# B3PIC_picfinalcurrentreading.net
KiCad netlist of a schematic drawn in EAGLE
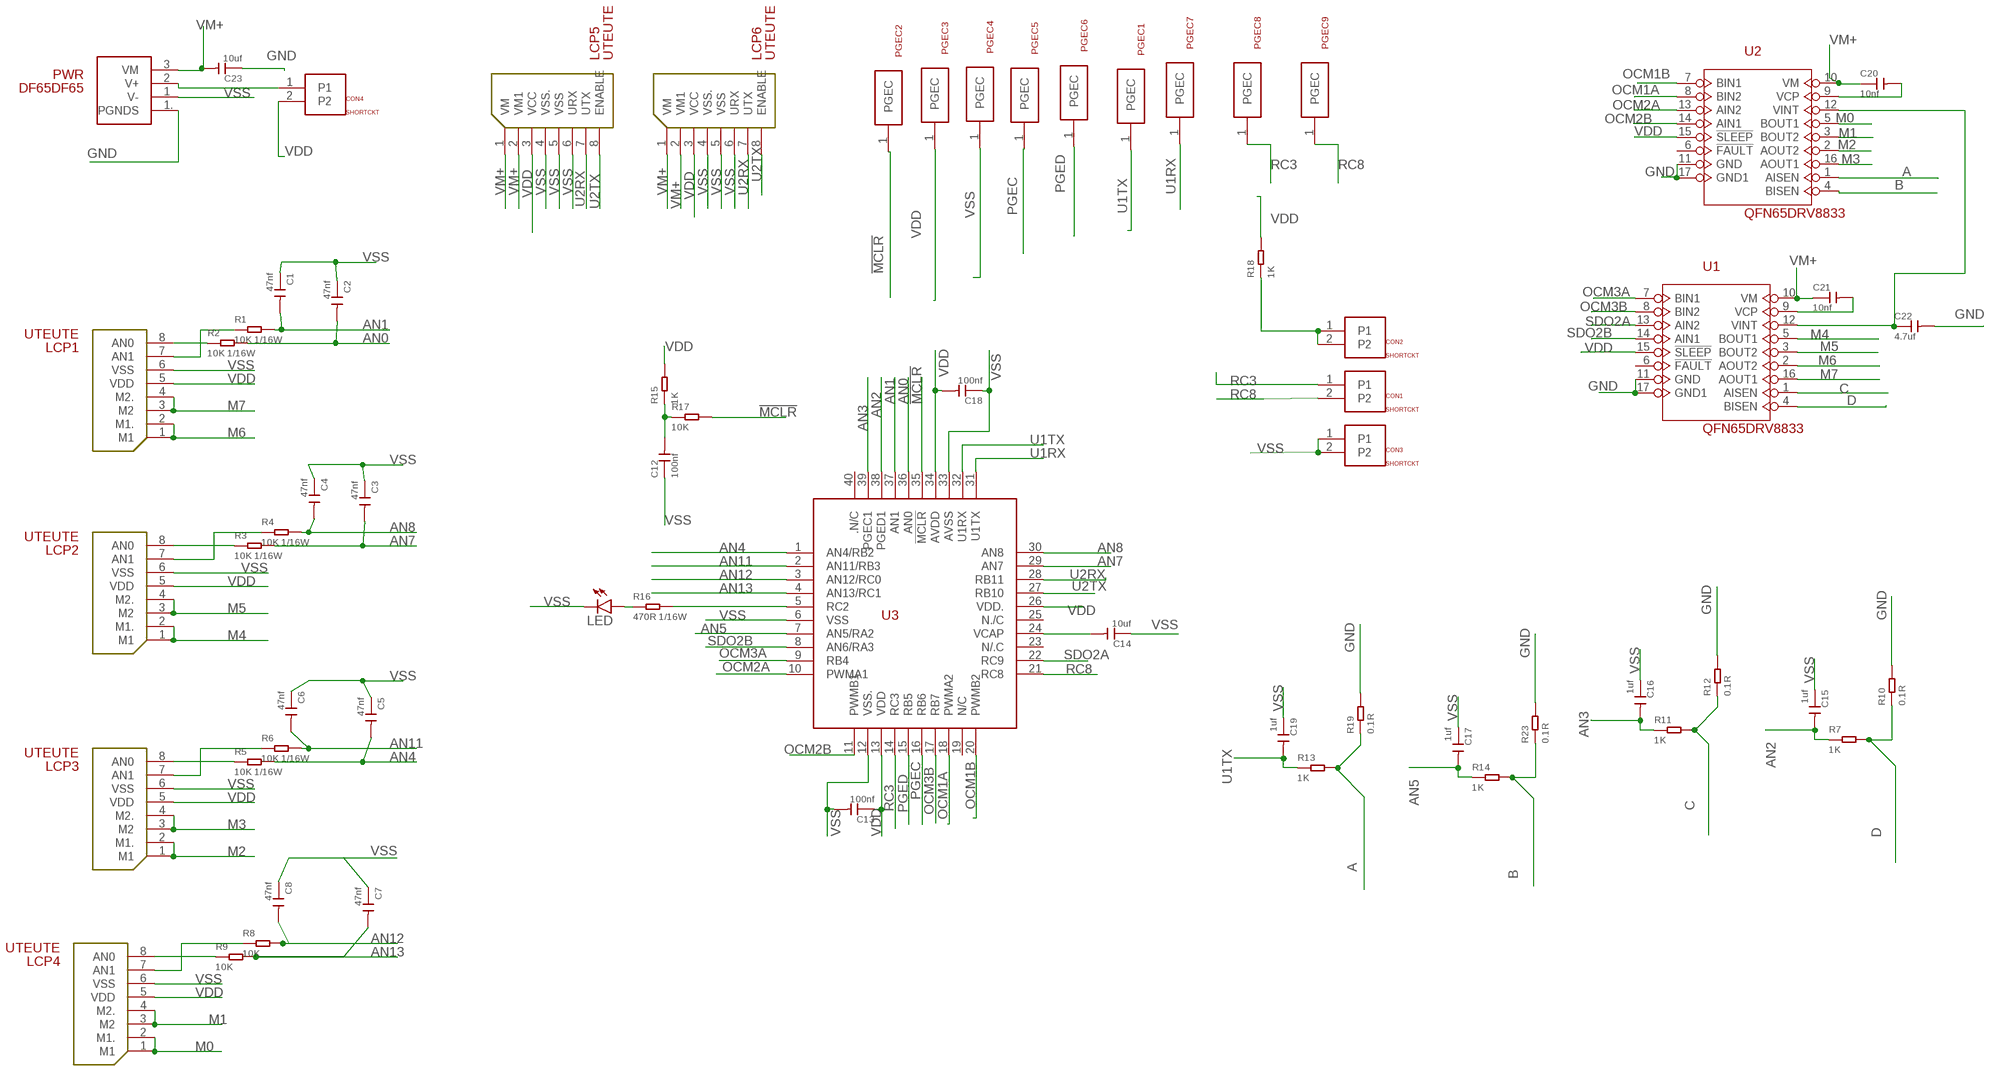
[diagram p0: schematic, sheet 1]

(export (version "E")
  (design (tool "Eeschema 10.0.6"))
  (components
    (comp (ref "C1")
      (value "47nf")
      (footprint "eagle-import:C0402")
      (fields (field (name "MPN") "CC0402KRX7R8BB473"))
      (libsource (lib "eagle-import") (part "CERAMIC-47NF-25V-10%-X7R(0402)"))
    )
    (comp (ref "C2")
      (value "47nf")
      (footprint "eagle-import:C0402")
      (fields (field (name "MPN") "CC0402KRX7R8BB473"))
      (libsource (lib "eagle-import") (part "CERAMIC-47NF-25V-10%-X7R(0402)"))
    )
    (comp (ref "C3")
      (value "47nf")
      (footprint "eagle-import:C0402")
      (fields (field (name "MPN") "CC0402KRX7R8BB473"))
      (libsource (lib "eagle-import") (part "CERAMIC-47NF-25V-10%-X7R(0402)"))
    )
    (comp (ref "C4")
      (value "47nf")
      (footprint "eagle-import:C0402")
      (fields (field (name "MPN") "CC0402KRX7R8BB473"))
      (libsource (lib "eagle-import") (part "CERAMIC-47NF-25V-10%-X7R(0402)"))
    )
    (comp (ref "C5")
      (value "47nf")
      (footprint "eagle-import:C0402")
      (fields (field (name "MPN") "CC0402KRX7R8BB473"))
      (libsource (lib "eagle-import") (part "CERAMIC-47NF-25V-10%-X7R(0402)"))
    )
    (comp (ref "C6")
      (value "47nf")
      (footprint "eagle-import:C0402")
      (fields (field (name "MPN") "CC0402KRX7R8BB473"))
      (libsource (lib "eagle-import") (part "CERAMIC-47NF-25V-10%-X7R(0402)"))
    )
    (comp (ref "C7")
      (value "47nf")
      (footprint "eagle-import:C0402")
      (fields (field (name "MPN") "CC0402KRX7R8BB473"))
      (libsource (lib "eagle-import") (part "CERAMIC-47NF-25V-10%-X7R(0402)"))
    )
    (comp (ref "C8")
      (value "47nf")
      (footprint "eagle-import:C0402")
      (fields (field (name "MPN") "CC0402KRX7R8BB473"))
      (libsource (lib "eagle-import") (part "CERAMIC-47NF-25V-10%-X7R(0402)"))
    )
    (comp (ref "C12")
      (value "100nf")
      (footprint "eagle-import:C0402")
      (fields (field (name "MPN") "CC0402KRX7R8BB104"))
      (libsource (lib "eagle-import") (part "CERAMIC-100NF-25V-10%-X7R(0402)"))
    )
    (comp (ref "C13")
      (value "100nf")
      (footprint "eagle-import:C0402")
      (fields (field (name "MPN") "CC0402KRX7R8BB104"))
      (libsource (lib "eagle-import") (part "CERAMIC-100NF-25V-10%-X7R(0402)"))
    )
    (comp (ref "C14")
      (value "10uf")
      (footprint "eagle-import:C0402")
      (fields (field (name "MPN") "CC0402MRX5R5BB106"))
      (libsource (lib "eagle-import") (part "CERAMIC-10UF-6.3V-20%-X5R(0402)"))
    )
    (comp (ref "C15")
      (value "1uf")
      (footprint "eagle-import:C0402")
      (fields (field (name "MPN") "CC0402KRX5R6BB105"))
      (libsource (lib "eagle-import") (part "CERAMIC-1UF-10V-10%-X5R(0402)"))
    )
    (comp (ref "C16")
      (value "1uf")
      (footprint "eagle-import:C0402")
      (fields (field (name "MPN") "CC0402KRX5R6BB105"))
      (libsource (lib "eagle-import") (part "CERAMIC-1UF-10V-10%-X5R(0402)"))
    )
    (comp (ref "C17")
      (value "1uf")
      (footprint "eagle-import:C0402")
      (fields (field (name "MPN") "CC0402KRX5R6BB105"))
      (libsource (lib "eagle-import") (part "CERAMIC-1UF-10V-10%-X5R(0402)"))
    )
    (comp (ref "C18")
      (value "100nf")
      (footprint "eagle-import:C0402")
      (fields (field (name "MPN") "CC0402KRX7R8BB104"))
      (libsource (lib "eagle-import") (part "CERAMIC-100NF-25V-10%-X7R(0402)"))
    )
    (comp (ref "C19")
      (value "1uf")
      (footprint "eagle-import:C0402")
      (fields (field (name "MPN") "CC0402KRX5R6BB105"))
      (libsource (lib "eagle-import") (part "CERAMIC-1UF-10V-10%-X5R(0402)"))
    )
    (comp (ref "C20")
      (value "10nf")
      (footprint "eagle-import:C0402")
      (fields (field (name "MPN") "CC0402KRX7R9BB103"))
      (libsource (lib "eagle-import") (part "CERAMIC-10NF-50V-10%-X7R(0402)"))
    )
    (comp (ref "C21")
      (value "10nf")
      (footprint "eagle-import:C0402")
      (fields (field (name "MPN") "CC0402KRX7R9BB103"))
      (libsource (lib "eagle-import") (part "CERAMIC-10NF-50V-10%-X7R(0402)"))
    )
    (comp (ref "C22")
      (value "4.7uf")
      (footprint "eagle-import:C0402")
      (fields (field (name "MPN") "CC0402MRX5R5BB475"))
      (libsource (lib "eagle-import") (part "CERAMIC-4.7UF-6.3V-20%-X5R(0402)"))
    )
    (comp (ref "C23")
      (value "10uf")
      (footprint "eagle-import:C0402")
      (fields (field (name "MPN") "CC0402MRX5R5BB106"))
      (libsource (lib "eagle-import") (part "CERAMIC-10UF-6.3V-20%-X5R(0402)"))
    )
    (comp (ref "CON1")
      (value "SHORTCKT")
      (footprint "eagle-import:SHORT")
      (libsource (lib "eagle-import") (part "SHORTCKT"))
    )
    (comp (ref "CON2")
      (value "SHORTCKT")
      (footprint "eagle-import:SHORT")
      (libsource (lib "eagle-import") (part "SHORTCKT"))
    )
    (comp (ref "CON3")
      (value "SHORTCKT")
      (footprint "eagle-import:SHORT")
      (libsource (lib "eagle-import") (part "SHORTCKT"))
    )
    (comp (ref "CON4")
      (value "SHORTCKT")
      (footprint "eagle-import:SHORT")
      (libsource (lib "eagle-import") (part "SHORTCKT"))
    )
    (comp (ref "LCP1")
      (value "UTEUTE")
      (footprint "eagle-import:UTE")
      (libsource (lib "eagle-import") (part "UTEUTE"))
    )
    (comp (ref "LCP2")
      (value "UTEUTE")
      (footprint "eagle-import:UTE")
      (libsource (lib "eagle-import") (part "UTEUTE"))
    )
    (comp (ref "LCP3")
      (value "UTEUTE")
      (footprint "eagle-import:UTE")
      (libsource (lib "eagle-import") (part "UTEUTE"))
    )
    (comp (ref "LCP4")
      (value "UTEUTE")
      (footprint "eagle-import:UTE")
      (libsource (lib "eagle-import") (part "UTEUTE"))
    )
    (comp (ref "LCP5")
      (value "UTEUTE")
      (footprint "eagle-import:UTE")
      (libsource (lib "eagle-import") (part "ute5526(uart)_UTEUTE"))
    )
    (comp (ref "LCP6")
      (value "UTEUTE")
      (footprint "eagle-import:UTE")
      (libsource (lib "eagle-import") (part "ute5526(uart)_UTEUTE"))
    )
    (comp (ref "LED")
      (value "LEDCHIP-LED0603")
      (footprint "eagle-import:CHIP-LED0603")
      (libsource (lib "eagle-import") (part "LEDCHIP-LED0603"))
    )
    (comp (ref "PGEC1")
      (value "PGECPGEC")
      (footprint "eagle-import:PGEC")
      (libsource (lib "eagle-import") (part "PGECPGEC"))
    )
    (comp (ref "PGEC2")
      (value "PGECPGEC")
      (footprint "eagle-import:PGEC")
      (libsource (lib "eagle-import") (part "PGECPGEC"))
    )
    (comp (ref "PGEC3")
      (value "PGECPGEC")
      (footprint "eagle-import:PGEC")
      (libsource (lib "eagle-import") (part "PGECPGEC"))
    )
    (comp (ref "PGEC4")
      (value "PGECPGEC")
      (footprint "eagle-import:PGEC")
      (libsource (lib "eagle-import") (part "PGECPGEC"))
    )
    (comp (ref "PGEC5")
      (value "PGECPGEC")
      (footprint "eagle-import:PGEC")
      (libsource (lib "eagle-import") (part "PGECPGEC"))
    )
    (comp (ref "PGEC6")
      (value "PGECPGEC")
      (footprint "eagle-import:PGEC")
      (libsource (lib "eagle-import") (part "PGECPGEC"))
    )
    (comp (ref "PGEC7")
      (value "PGECPGEC")
      (footprint "eagle-import:PGEC")
      (libsource (lib "eagle-import") (part "PGECPGEC"))
    )
    (comp (ref "PGEC8")
      (value "PGECPGEC")
      (footprint "eagle-import:PGEC")
      (libsource (lib "eagle-import") (part "PGECPGEC"))
    )
    (comp (ref "PGEC9")
      (value "PGECPGEC")
      (footprint "eagle-import:PGEC")
      (libsource (lib "eagle-import") (part "PGECPGEC"))
    )
    (comp (ref "PWR")
      (value "DF65DF65")
      (footprint "eagle-import:DF65")
      (libsource (lib "eagle-import") (part "DF65DF65"))
    )
    (comp (ref "R1")
      (value "10K 1/16W")
      (footprint "eagle-import:R0402")
      (fields (field (name "MPN") "RC0402FR-0710KL"))
      (libsource (lib "eagle-import") (part "SMD-RES-10K-1%-1/16W(0402)"))
    )
    (comp (ref "R2")
      (value "10K 1/16W")
      (footprint "eagle-import:R0402")
      (fields (field (name "MPN") "RC0402FR-0710KL"))
      (libsource (lib "eagle-import") (part "SMD-RES-10K-1%-1/16W(0402)"))
    )
    (comp (ref "R3")
      (value "10K 1/16W")
      (footprint "eagle-import:R0402")
      (fields (field (name "MPN") "RC0402FR-0710KL"))
      (libsource (lib "eagle-import") (part "SMD-RES-10K-1%-1/16W(0402)"))
    )
    (comp (ref "R4")
      (value "10K 1/16W")
      (footprint "eagle-import:R0402")
      (fields (field (name "MPN") "RC0402FR-0710KL"))
      (libsource (lib "eagle-import") (part "SMD-RES-10K-1%-1/16W(0402)"))
    )
    (comp (ref "R5")
      (value "10K 1/16W")
      (footprint "eagle-import:R0402")
      (fields (field (name "MPN") "RC0402FR-0710KL"))
      (libsource (lib "eagle-import") (part "SMD-RES-10K-1%-1/16W(0402)"))
    )
    (comp (ref "R6")
      (value "10K 1/16W")
      (footprint "eagle-import:R0402")
      (fields (field (name "MPN") "RC0402FR-0710KL"))
      (libsource (lib "eagle-import") (part "SMD-RES-10K-1%-1/16W(0402)"))
    )
    (comp (ref "R7")
      (value "1K")
      (footprint "eagle-import:R0402")
      (fields (field (name "MPN") "RC0402JR-071KL"))
      (libsource (lib "eagle-import") (part "SMD-RES-1K-5%-1/16W(0402)"))
    )
    (comp (ref "R8")
      (value "10K")
      (footprint "eagle-import:R0402")
      (fields (field (name "MPN") "RC0402JR-0710KL"))
      (libsource (lib "eagle-import") (part "SMD-RES-10K-5%-1/(0402)"))
    )
    (comp (ref "R9")
      (value "10K")
      (footprint "eagle-import:R0402")
      (fields (field (name "MPN") "RC0402JR-0710KL"))
      (libsource (lib "eagle-import") (part "SMD-RES-10K-5%-1/(0402)"))
    )
    (comp (ref "R10")
      (value "0.1R")
      (footprint "eagle-import:R0805")
      (fields (field (name "MPN") "RL0805JR-070R1L"))
      (libsource (lib "eagle-import") (part "SMD-RES-0.1R-5%-1/8W(0805)"))
    )
    (comp (ref "R11")
      (value "1K")
      (footprint "eagle-import:R0402")
      (fields (field (name "MPN") "RC0402JR-071KL"))
      (libsource (lib "eagle-import") (part "SMD-RES-1K-5%-1/16W(0402)"))
    )
    (comp (ref "R12")
      (value "0.1R")
      (footprint "eagle-import:R0805")
      (fields (field (name "MPN") "RL0805JR-070R1L"))
      (libsource (lib "eagle-import") (part "SMD-RES-0.1R-5%-1/8W(0805)"))
    )
    (comp (ref "R13")
      (value "1K")
      (footprint "eagle-import:R0402")
      (fields (field (name "MPN") "RC0402JR-071KL"))
      (libsource (lib "eagle-import") (part "SMD-RES-1K-5%-1/16W(0402)"))
    )
    (comp (ref "R14")
      (value "1K")
      (footprint "eagle-import:R0402")
      (fields (field (name "MPN") "RC0402JR-071KL"))
      (libsource (lib "eagle-import") (part "SMD-RES-1K-5%-1/16W(0402)"))
    )
    (comp (ref "R15")
      (value "1K")
      (footprint "eagle-import:R0402")
      (fields (field (name "MPN") "RC0402JR-071KL"))
      (libsource (lib "eagle-import") (part "SMD-RES-1K-5%-1/16W(0402)"))
    )
    (comp (ref "R16")
      (value "470R 1/16W")
      (footprint "eagle-import:R0402")
      (fields (field (name "MPN") "RC0402JR-07470RL"))
      (libsource (lib "eagle-import") (part "SMD-RES-470R-5%-1/16W(0402)"))
    )
    (comp (ref "R17")
      (value "10K")
      (footprint "eagle-import:R0402")
      (fields (field (name "MPN") "RC0402JR-0710KL"))
      (libsource (lib "eagle-import") (part "SMD-RES-10K-5%-1/(0402)"))
    )
    (comp (ref "R18")
      (value "1K")
      (footprint "eagle-import:R0402")
      (fields (field (name "MPN") "RC0402JR-071KL"))
      (libsource (lib "eagle-import") (part "SMD-RES-1K-5%-1/16W(0402)"))
    )
    (comp (ref "R19")
      (value "0.1R")
      (footprint "eagle-import:R0805")
      (fields (field (name "MPN") "RL0805JR-070R1L"))
      (libsource (lib "eagle-import") (part "SMD-RES-0.1R-5%-1/8W(0805)"))
    )
    (comp (ref "R23")
      (value "0.1R")
      (footprint "eagle-import:R0805")
      (fields (field (name "MPN") "RL0805JR-070R1L"))
      (libsource (lib "eagle-import") (part "SMD-RES-0.1R-5%-1/8W(0805)"))
    )
    (comp (ref "U1")
      (value "QFN65DRV8833")
      (footprint "eagle-import:QFN65P400X400X80-17N")
      (libsource (lib "eagle-import") (part "QFN65DRV8833"))
    )
    (comp (ref "U2")
      (value "QFN65DRV8833")
      (footprint "eagle-import:QFN65P400X400X80-17N")
      (libsource (lib "eagle-import") (part "QFN65DRV8833"))
    )
    (comp (ref "U3")
      (value "PIC32MM0064GPL036PIC32MM0064GPL36")
      (footprint "eagle-import:UQFN40MV5X5MM")
      (libsource (lib "eagle-import") (part "PIC32MM0064GPL036PIC32MM0064GPL36"))
    )
  )
  (nets
    (net (code "1") (name "/A") (class "Default")
      (node (ref "R13") (pin "2") (pinfunction "2_2") (pintype "passive"))
      (node (ref "R19") (pin "1") (pinfunction "1_1") (pintype "passive"))
      (node (ref "U2") (pin "1") (pinfunction "AISEN_1") (pintype "bidirectional"))
    )
    (net (code "2") (name "/AN0") (class "Default")
      (node (ref "C2") (pin "2") (pinfunction "2_2") (pintype "passive"))
      (node (ref "R2") (pin "2") (pinfunction "2_2") (pintype "passive"))
      (node (ref "U3") (pin "36") (pinfunction "AN0_36") (pintype "bidirectional"))
    )
    (net (code "3") (name "/AN1") (class "Default")
      (node (ref "C1") (pin "2") (pinfunction "2_2") (pintype "passive"))
      (node (ref "R1") (pin "2") (pinfunction "2_2") (pintype "passive"))
      (node (ref "U3") (pin "37") (pinfunction "AN1_37") (pintype "bidirectional"))
    )
    (net (code "4") (name "/AN2") (class "Default")
      (node (ref "C15") (pin "2") (pinfunction "2_2") (pintype "passive"))
      (node (ref "R7") (pin "1") (pinfunction "1_1") (pintype "passive"))
      (node (ref "U3") (pin "38") (pinfunction "PGED1_38") (pintype "bidirectional"))
    )
    (net (code "5") (name "/AN3") (class "Default")
      (node (ref "C16") (pin "2") (pinfunction "2_2") (pintype "passive"))
      (node (ref "R11") (pin "1") (pinfunction "1_1") (pintype "passive"))
      (node (ref "U3") (pin "39") (pinfunction "PGEC1_39") (pintype "bidirectional"))
    )
    (net (code "6") (name "/AN4") (class "Default")
      (node (ref "C5") (pin "2") (pinfunction "2_2") (pintype "passive"))
      (node (ref "R5") (pin "2") (pinfunction "2_2") (pintype "passive"))
      (node (ref "U3") (pin "1") (pinfunction "AN4/RB2_1") (pintype "bidirectional"))
    )
    (net (code "7") (name "/AN5") (class "Default")
      (node (ref "C17") (pin "2") (pinfunction "2_2") (pintype "passive"))
      (node (ref "R14") (pin "1") (pinfunction "1_1") (pintype "passive"))
      (node (ref "U3") (pin "7") (pinfunction "AN5/RA2_7") (pintype "bidirectional"))
    )
    (net (code "8") (name "/AN7") (class "Default")
      (node (ref "C3") (pin "2") (pinfunction "2_2") (pintype "passive"))
      (node (ref "R3") (pin "2") (pinfunction "2_2") (pintype "passive"))
      (node (ref "U3") (pin "29") (pinfunction "AN7_29") (pintype "bidirectional"))
    )
    (net (code "9") (name "/AN8") (class "Default")
      (node (ref "C4") (pin "2") (pinfunction "2_2") (pintype "passive"))
      (node (ref "R4") (pin "2") (pinfunction "2_2") (pintype "passive"))
      (node (ref "U3") (pin "30") (pinfunction "AN8_30") (pintype "bidirectional"))
    )
    (net (code "10") (name "/AN11") (class "Default")
      (node (ref "C6") (pin "2") (pinfunction "2_2") (pintype "passive"))
      (node (ref "R6") (pin "2") (pinfunction "2_2") (pintype "passive"))
      (node (ref "U3") (pin "2") (pinfunction "AN11/RB3_2") (pintype "bidirectional"))
    )
    (net (code "11") (name "/AN12") (class "Default")
      (node (ref "C8") (pin "2") (pinfunction "2_2") (pintype "passive"))
      (node (ref "R8") (pin "2") (pinfunction "2_2") (pintype "passive"))
      (node (ref "U3") (pin "3") (pinfunction "AN12/RC0_3") (pintype "bidirectional"))
    )
    (net (code "12") (name "/AN13") (class "Default")
      (node (ref "C7") (pin "2") (pinfunction "2_2") (pintype "passive"))
      (node (ref "R9") (pin "2") (pinfunction "2_2") (pintype "passive"))
      (node (ref "U3") (pin "4") (pinfunction "AN13/RC1_4") (pintype "bidirectional"))
    )
    (net (code "13") (name "/B") (class "Default")
      (node (ref "R14") (pin "2") (pinfunction "2_2") (pintype "passive"))
      (node (ref "R23") (pin "1") (pinfunction "1_1") (pintype "passive"))
      (node (ref "U2") (pin "4") (pinfunction "BISEN_4") (pintype "bidirectional"))
    )
    (net (code "14") (name "/C") (class "Default")
      (node (ref "R11") (pin "2") (pinfunction "2_2") (pintype "passive"))
      (node (ref "R12") (pin "1") (pinfunction "1_1") (pintype "passive"))
      (node (ref "U1") (pin "1") (pinfunction "AISEN_1") (pintype "bidirectional"))
    )
    (net (code "15") (name "/D") (class "Default")
      (node (ref "R10") (pin "1") (pinfunction "1_1") (pintype "passive"))
      (node (ref "R7") (pin "2") (pinfunction "2_2") (pintype "passive"))
      (node (ref "U1") (pin "4") (pinfunction "BISEN_4") (pintype "bidirectional"))
    )
    (net (code "16") (name "/GND") (class "Default")
      (node (ref "C22") (pin "2") (pinfunction "2_2") (pintype "passive"))
      (node (ref "C23") (pin "1") (pinfunction "1_1") (pintype "passive"))
      (node (ref "PWR") (pin "1.") (pinfunction "PGNDS_1.") (pintype "bidirectional"))
      (node (ref "R10") (pin "2") (pinfunction "2_2") (pintype "passive"))
      (node (ref "R12") (pin "2") (pinfunction "2_2") (pintype "passive"))
      (node (ref "R19") (pin "2") (pinfunction "2_2") (pintype "passive"))
      (node (ref "R23") (pin "2") (pinfunction "2_2") (pintype "passive"))
      (node (ref "U1") (pin "11") (pinfunction "GND_11") (pintype "bidirectional"))
      (node (ref "U1") (pin "17") (pinfunction "GND1_17") (pintype "bidirectional"))
      (node (ref "U2") (pin "11") (pinfunction "GND_11") (pintype "bidirectional"))
      (node (ref "U2") (pin "17") (pinfunction "GND1_17") (pintype "bidirectional"))
    )
    (net (code "17") (name "/M0") (class "Default")
      (node (ref "LCP4") (pin "1") (pinfunction "M1_1") (pintype "bidirectional"))
      (node (ref "LCP4") (pin "2") (pinfunction "M1._2") (pintype "bidirectional"))
      (node (ref "U2") (pin "5") (pinfunction "BOUT1_5") (pintype "bidirectional"))
    )
    (net (code "18") (name "/M1") (class "Default")
      (node (ref "LCP4") (pin "3") (pinfunction "M2_3") (pintype "bidirectional"))
      (node (ref "LCP4") (pin "4") (pinfunction "M2._4") (pintype "bidirectional"))
      (node (ref "U2") (pin "3") (pinfunction "BOUT2_3") (pintype "bidirectional"))
    )
    (net (code "19") (name "/M2") (class "Default")
      (node (ref "LCP3") (pin "1") (pinfunction "M1_1") (pintype "bidirectional"))
      (node (ref "LCP3") (pin "2") (pinfunction "M1._2") (pintype "bidirectional"))
      (node (ref "U2") (pin "2") (pinfunction "AOUT2_2") (pintype "bidirectional"))
    )
    (net (code "20") (name "/M3") (class "Default")
      (node (ref "LCP3") (pin "3") (pinfunction "M2_3") (pintype "bidirectional"))
      (node (ref "LCP3") (pin "4") (pinfunction "M2._4") (pintype "bidirectional"))
      (node (ref "U2") (pin "16") (pinfunction "AOUT1_16") (pintype "bidirectional"))
    )
    (net (code "21") (name "/M4") (class "Default")
      (node (ref "LCP2") (pin "1") (pinfunction "M1_1") (pintype "bidirectional"))
      (node (ref "LCP2") (pin "2") (pinfunction "M1._2") (pintype "bidirectional"))
      (node (ref "U1") (pin "5") (pinfunction "BOUT1_5") (pintype "bidirectional"))
    )
    (net (code "22") (name "/M5") (class "Default")
      (node (ref "LCP2") (pin "3") (pinfunction "M2_3") (pintype "bidirectional"))
      (node (ref "LCP2") (pin "4") (pinfunction "M2._4") (pintype "bidirectional"))
      (node (ref "U1") (pin "3") (pinfunction "BOUT2_3") (pintype "bidirectional"))
    )
    (net (code "23") (name "/M6") (class "Default")
      (node (ref "LCP1") (pin "1") (pinfunction "M1_1") (pintype "bidirectional"))
      (node (ref "LCP1") (pin "2") (pinfunction "M1._2") (pintype "bidirectional"))
      (node (ref "U1") (pin "2") (pinfunction "AOUT2_2") (pintype "bidirectional"))
    )
    (net (code "24") (name "/M7") (class "Default")
      (node (ref "LCP1") (pin "3") (pinfunction "M2_3") (pintype "bidirectional"))
      (node (ref "LCP1") (pin "4") (pinfunction "M2._4") (pintype "bidirectional"))
      (node (ref "U1") (pin "16") (pinfunction "AOUT1_16") (pintype "bidirectional"))
    )
    (net (code "25") (name "/OCM1A") (class "Default")
      (node (ref "U2") (pin "8") (pinfunction "BIN2_8") (pintype "bidirectional"))
      (node (ref "U3") (pin "18") (pinfunction "PWMA2_18") (pintype "bidirectional"))
    )
    (net (code "26") (name "/OCM1B") (class "Default")
      (node (ref "U2") (pin "7") (pinfunction "BIN1_7") (pintype "bidirectional"))
      (node (ref "U3") (pin "20") (pinfunction "PWMB2_20") (pintype "bidirectional"))
    )
    (net (code "27") (name "/OCM2A") (class "Default")
      (node (ref "U2") (pin "13") (pinfunction "AIN2_13") (pintype "bidirectional"))
      (node (ref "U3") (pin "10") (pinfunction "PWMA1_10") (pintype "bidirectional"))
    )
    (net (code "28") (name "/OCM2B") (class "Default")
      (node (ref "U2") (pin "14") (pinfunction "AIN1_14") (pintype "bidirectional"))
      (node (ref "U3") (pin "11") (pinfunction "PWMB1_11") (pintype "bidirectional"))
    )
    (net (code "29") (name "/OCM3A") (class "Default")
      (node (ref "U1") (pin "7") (pinfunction "BIN1_7") (pintype "bidirectional"))
      (node (ref "U3") (pin "9") (pinfunction "RB4_9") (pintype "bidirectional"))
    )
    (net (code "30") (name "/OCM3B") (class "Default")
      (node (ref "U1") (pin "8") (pinfunction "BIN2_8") (pintype "bidirectional"))
      (node (ref "U3") (pin "17") (pinfunction "RB7_17") (pintype "bidirectional"))
    )
    (net (code "31") (name "/PGEC") (class "Default")
      (node (ref "PGEC5") (pin "1") (pinfunction "PGEC_1") (pintype "bidirectional"))
      (node (ref "U3") (pin "16") (pinfunction "RB6_16") (pintype "bidirectional"))
    )
    (net (code "32") (name "/PGED") (class "Default")
      (node (ref "PGEC6") (pin "1") (pinfunction "PGEC_1") (pintype "bidirectional"))
      (node (ref "U3") (pin "15") (pinfunction "RB5_15") (pintype "bidirectional"))
    )
    (net (code "33") (name "/RC3") (class "Default")
      (node (ref "CON1") (pin "1") (pinfunction "P1_1") (pintype "bidirectional"))
      (node (ref "PGEC8") (pin "1") (pinfunction "PGEC_1") (pintype "bidirectional"))
      (node (ref "U3") (pin "14") (pinfunction "RC3_14") (pintype "bidirectional"))
    )
    (net (code "34") (name "/RC8") (class "Default")
      (node (ref "CON1") (pin "2") (pinfunction "P2_2") (pintype "bidirectional"))
      (node (ref "PGEC9") (pin "1") (pinfunction "PGEC_1") (pintype "bidirectional"))
      (node (ref "U3") (pin "21") (pinfunction "RC8_21") (pintype "bidirectional"))
    )
    (net (code "35") (name "/SDO2A") (class "Default")
      (node (ref "U1") (pin "13") (pinfunction "AIN2_13") (pintype "bidirectional"))
      (node (ref "U3") (pin "22") (pinfunction "RC9_22") (pintype "bidirectional"))
    )
    (net (code "36") (name "/SDO2B") (class "Default")
      (node (ref "U1") (pin "14") (pinfunction "AIN1_14") (pintype "bidirectional"))
      (node (ref "U3") (pin "8") (pinfunction "AN6/RA3_8") (pintype "bidirectional"))
    )
    (net (code "37") (name "/U1RX") (class "Default")
      (node (ref "PGEC7") (pin "1") (pinfunction "PGEC_1") (pintype "bidirectional"))
      (node (ref "U3") (pin "31") (pinfunction "U1TX_31") (pintype "bidirectional"))
    )
    (net (code "38") (name "/U1TX") (class "Default")
      (node (ref "C19") (pin "2") (pinfunction "2_2") (pintype "passive"))
      (node (ref "PGEC1") (pin "1") (pinfunction "PGEC_1") (pintype "bidirectional"))
      (node (ref "R13") (pin "1") (pinfunction "1_1") (pintype "passive"))
      (node (ref "U3") (pin "32") (pinfunction "U1RX_32") (pintype "bidirectional"))
    )
    (net (code "39") (name "/U2RX") (class "Default")
      (node (ref "LCP5") (pin "7") (pinfunction "UTX_7") (pintype "bidirectional"))
      (node (ref "LCP6") (pin "7") (pinfunction "UTX_7") (pintype "bidirectional"))
      (node (ref "U3") (pin "28") (pinfunction "RB11_28") (pintype "bidirectional"))
    )
    (net (code "40") (name "/U2TX") (class "Default")
      (node (ref "LCP5") (pin "8") (pinfunction "ENABLE_8") (pintype "bidirectional"))
      (node (ref "LCP6") (pin "8") (pinfunction "ENABLE_8") (pintype "bidirectional"))
      (node (ref "U3") (pin "27") (pinfunction "RB10_27") (pintype "bidirectional"))
    )
    (net (code "41") (name "/VDD") (class "Default")
      (node (ref "C13") (pin "1") (pinfunction "1_1") (pintype "passive"))
      (node (ref "C18") (pin "2") (pinfunction "2_2") (pintype "passive"))
      (node (ref "CON4") (pin "2") (pinfunction "P2_2") (pintype "bidirectional"))
      (node (ref "LCP1") (pin "5") (pinfunction "VDD_5") (pintype "bidirectional"))
      (node (ref "LCP2") (pin "5") (pinfunction "VDD_5") (pintype "bidirectional"))
      (node (ref "LCP3") (pin "5") (pinfunction "VDD_5") (pintype "bidirectional"))
      (node (ref "LCP4") (pin "5") (pinfunction "VDD_5") (pintype "bidirectional"))
      (node (ref "LCP5") (pin "3") (pinfunction "VCC_3") (pintype "bidirectional"))
      (node (ref "LCP6") (pin "3") (pinfunction "VCC_3") (pintype "bidirectional"))
      (node (ref "PGEC3") (pin "1") (pinfunction "PGEC_1") (pintype "bidirectional"))
      (node (ref "R15") (pin "2") (pinfunction "2_2") (pintype "passive"))
      (node (ref "R18") (pin "2") (pinfunction "2_2") (pintype "passive"))
      (node (ref "U1") (pin "15") (pinfunction "~{SLEEP}_15") (pintype "bidirectional"))
      (node (ref "U2") (pin "15") (pinfunction "~{SLEEP}_15") (pintype "bidirectional"))
      (node (ref "U3") (pin "13") (pinfunction "VDD_13") (pintype "bidirectional"))
      (node (ref "U3") (pin "26") (pinfunction "VDD._26") (pintype "bidirectional"))
      (node (ref "U3") (pin "34") (pinfunction "AVDD_34") (pintype "bidirectional"))
    )
    (net (code "42") (name "/VM+") (class "Default")
      (node (ref "C20") (pin "1") (pinfunction "1_1") (pintype "passive"))
      (node (ref "C21") (pin "1") (pinfunction "1_1") (pintype "passive"))
      (node (ref "C23") (pin "2") (pinfunction "2_2") (pintype "passive"))
      (node (ref "LCP5") (pin "1") (pinfunction "VM_1") (pintype "bidirectional"))
      (node (ref "LCP5") (pin "2") (pinfunction "VM1_2") (pintype "bidirectional"))
      (node (ref "LCP6") (pin "1") (pinfunction "VM_1") (pintype "bidirectional"))
      (node (ref "LCP6") (pin "2") (pinfunction "VM1_2") (pintype "bidirectional"))
      (node (ref "PWR") (pin "3") (pinfunction "VM_3") (pintype "bidirectional"))
      (node (ref "U1") (pin "10") (pinfunction "VM_10") (pintype "bidirectional"))
      (node (ref "U2") (pin "10") (pinfunction "VM_10") (pintype "bidirectional"))
    )
    (net (code "43") (name "/VSS") (class "Default")
      (node (ref "C1") (pin "1") (pinfunction "1_1") (pintype "passive"))
      (node (ref "C12") (pin "1") (pinfunction "1_1") (pintype "passive"))
      (node (ref "C13") (pin "2") (pinfunction "2_2") (pintype "passive"))
      (node (ref "C14") (pin "1") (pinfunction "1_1") (pintype "passive"))
      (node (ref "C15") (pin "1") (pinfunction "1_1") (pintype "passive"))
      (node (ref "C16") (pin "1") (pinfunction "1_1") (pintype "passive"))
      (node (ref "C17") (pin "1") (pinfunction "1_1") (pintype "passive"))
      (node (ref "C18") (pin "1") (pinfunction "1_1") (pintype "passive"))
      (node (ref "C19") (pin "1") (pinfunction "1_1") (pintype "passive"))
      (node (ref "C2") (pin "1") (pinfunction "1_1") (pintype "passive"))
      (node (ref "C3") (pin "1") (pinfunction "1_1") (pintype "passive"))
      (node (ref "C4") (pin "1") (pinfunction "1_1") (pintype "passive"))
      (node (ref "C5") (pin "1") (pinfunction "1_1") (pintype "passive"))
      (node (ref "C6") (pin "1") (pinfunction "1_1") (pintype "passive"))
      (node (ref "C7") (pin "1") (pinfunction "1_1") (pintype "passive"))
      (node (ref "C8") (pin "1") (pinfunction "1_1") (pintype "passive"))
      (node (ref "CON3") (pin "1") (pinfunction "P1_1") (pintype "bidirectional"))
      (node (ref "CON3") (pin "2") (pinfunction "P2_2") (pintype "bidirectional"))
      (node (ref "LCP1") (pin "6") (pinfunction "VSS_6") (pintype "bidirectional"))
      (node (ref "LCP2") (pin "6") (pinfunction "VSS_6") (pintype "bidirectional"))
      (node (ref "LCP3") (pin "6") (pinfunction "VSS_6") (pintype "bidirectional"))
      (node (ref "LCP4") (pin "6") (pinfunction "VSS_6") (pintype "bidirectional"))
      (node (ref "LCP5") (pin "4") (pinfunction "VSS._4") (pintype "bidirectional"))
      (node (ref "LCP5") (pin "5") (pinfunction "VSS_5") (pintype "bidirectional"))
      (node (ref "LCP5") (pin "6") (pinfunction "URX_6") (pintype "bidirectional"))
      (node (ref "LCP6") (pin "4") (pinfunction "VSS._4") (pintype "bidirectional"))
      (node (ref "LCP6") (pin "5") (pinfunction "VSS_5") (pintype "bidirectional"))
      (node (ref "LCP6") (pin "6") (pinfunction "URX_6") (pintype "bidirectional"))
      (node (ref "LED") (pin "C") (pinfunction "C_C") (pintype "passive"))
      (node (ref "PGEC4") (pin "1") (pinfunction "PGEC_1") (pintype "bidirectional"))
      (node (ref "PWR") (pin "1") (pinfunction "V-_1") (pintype "bidirectional"))
      (node (ref "U3") (pin "12") (pinfunction "VSS._12") (pintype "bidirectional"))
      (node (ref "U3") (pin "33") (pinfunction "AVSS_33") (pintype "bidirectional"))
      (node (ref "U3") (pin "6") (pinfunction "VSS_6") (pintype "bidirectional"))
    )
    (net (code "44") (name "/~{MCLR}") (class "Default")
      (node (ref "PGEC2") (pin "1") (pinfunction "PGEC_1") (pintype "bidirectional"))
      (node (ref "R17") (pin "2") (pinfunction "2_2") (pintype "passive"))
      (node (ref "U3") (pin "35") (pinfunction "~{MCLR}_35") (pintype "bidirectional"))
    )
    (net (code "45") (name "Net-(C12-Pad2)") (class "Default")
      (node (ref "C12") (pin "2") (pinfunction "2_2") (pintype "passive"))
      (node (ref "R15") (pin "1") (pinfunction "1_1") (pintype "passive"))
      (node (ref "R17") (pin "1") (pinfunction "1_1") (pintype "passive"))
    )
    (net (code "46") (name "Net-(CON2-P1)") (class "Default")
      (node (ref "CON2") (pin "1") (pinfunction "P1_1") (pintype "bidirectional"))
      (node (ref "CON2") (pin "2") (pinfunction "P2_2") (pintype "bidirectional"))
      (node (ref "R18") (pin "1") (pinfunction "1_1") (pintype "passive"))
    )
    (net (code "47") (name "Net-(CON4-P1)") (class "Default")
      (node (ref "CON4") (pin "1") (pinfunction "P1_1") (pintype "bidirectional"))
      (node (ref "PWR") (pin "2") (pinfunction "V+_2") (pintype "bidirectional"))
    )
    (net (code "48") (name "Net-(LCP1-AN0)") (class "Default")
      (node (ref "LCP1") (pin "8") (pinfunction "AN0_8") (pintype "bidirectional"))
      (node (ref "R2") (pin "1") (pinfunction "1_1") (pintype "passive"))
    )
    (net (code "49") (name "Net-(LCP1-AN1)") (class "Default")
      (node (ref "LCP1") (pin "7") (pinfunction "AN1_7") (pintype "bidirectional"))
      (node (ref "R1") (pin "1") (pinfunction "1_1") (pintype "passive"))
    )
    (net (code "50") (name "Net-(LCP2-AN0)") (class "Default")
      (node (ref "LCP2") (pin "8") (pinfunction "AN0_8") (pintype "bidirectional"))
      (node (ref "R3") (pin "1") (pinfunction "1_1") (pintype "passive"))
    )
    (net (code "51") (name "Net-(LCP2-AN1)") (class "Default")
      (node (ref "LCP2") (pin "7") (pinfunction "AN1_7") (pintype "bidirectional"))
      (node (ref "R4") (pin "1") (pinfunction "1_1") (pintype "passive"))
    )
    (net (code "52") (name "Net-(LCP3-AN0)") (class "Default")
      (node (ref "LCP3") (pin "8") (pinfunction "AN0_8") (pintype "bidirectional"))
      (node (ref "R5") (pin "1") (pinfunction "1_1") (pintype "passive"))
    )
    (net (code "53") (name "Net-(LCP3-AN1)") (class "Default")
      (node (ref "LCP3") (pin "7") (pinfunction "AN1_7") (pintype "bidirectional"))
      (node (ref "R6") (pin "1") (pinfunction "1_1") (pintype "passive"))
    )
    (net (code "54") (name "Net-(LCP4-AN0)") (class "Default")
      (node (ref "LCP4") (pin "8") (pinfunction "AN0_8") (pintype "bidirectional"))
      (node (ref "R9") (pin "1") (pinfunction "1_1") (pintype "passive"))
    )
    (net (code "55") (name "Net-(LCP4-AN1)") (class "Default")
      (node (ref "LCP4") (pin "7") (pinfunction "AN1_7") (pintype "bidirectional"))
      (node (ref "R8") (pin "1") (pinfunction "1_1") (pintype "passive"))
    )
    (net (code "56") (name "Net-(LED-PadA)") (class "Default")
      (node (ref "LED") (pin "A") (pinfunction "A_A") (pintype "passive"))
      (node (ref "R16") (pin "1") (pinfunction "1_1") (pintype "passive"))
    )
    (net (code "57") (name "Net-(U1-VCP)") (class "Default")
      (node (ref "C21") (pin "2") (pinfunction "2_2") (pintype "passive"))
      (node (ref "U1") (pin "9") (pinfunction "VCP_9") (pintype "bidirectional"))
    )
    (net (code "58") (name "Net-(U1-VINT)") (class "Default")
      (node (ref "C22") (pin "1") (pinfunction "1_1") (pintype "passive"))
      (node (ref "U1") (pin "12") (pinfunction "VINT_12") (pintype "bidirectional"))
      (node (ref "U2") (pin "12") (pinfunction "VINT_12") (pintype "bidirectional"))
    )
    (net (code "59") (name "Net-(U2-VCP)") (class "Default")
      (node (ref "C20") (pin "2") (pinfunction "2_2") (pintype "passive"))
      (node (ref "U2") (pin "9") (pinfunction "VCP_9") (pintype "bidirectional"))
    )
    (net (code "60") (name "Net-(U3-RC2)") (class "Default")
      (node (ref "R16") (pin "2") (pinfunction "2_2") (pintype "passive"))
      (node (ref "U3") (pin "5") (pinfunction "RC2_5") (pintype "bidirectional"))
    )
    (net (code "61") (name "Net-(U3-VCAP)") (class "Default")
      (node (ref "C14") (pin "2") (pinfunction "2_2") (pintype "passive"))
      (node (ref "U3") (pin "24") (pinfunction "VCAP_24") (pintype "bidirectional"))
    )
    (net (code "62") (name "unconnected-(U1-~{FAULT}-Pad6)") (class "Default")
      (node (ref "U1") (pin "6") (pinfunction "~{FAULT}_6") (pintype "bidirectional"))
    )
    (net (code "63") (name "unconnected-(U2-~{FAULT}-Pad6)") (class "Default")
      (node (ref "U2") (pin "6") (pinfunction "~{FAULT}_6") (pintype "bidirectional"))
    )
    (net (code "64") (name "unconnected-(U3-.N{slash}C-Pad40)") (class "Default")
      (node (ref "U3") (pin "40") (pinfunction ".N/C_40") (pintype "bidirectional"))
    )
    (net (code "65") (name "unconnected-(U3-N.{slash}C-Pad25)") (class "Default")
      (node (ref "U3") (pin "25") (pinfunction "N./C_25") (pintype "bidirectional"))
    )
    (net (code "66") (name "unconnected-(U3-N{slash}.C-Pad23)") (class "Default")
      (node (ref "U3") (pin "23") (pinfunction "N/.C_23") (pintype "bidirectional"))
    )
    (net (code "67") (name "unconnected-(U3-N{slash}C-Pad19)") (class "Default")
      (node (ref "U3") (pin "19") (pinfunction "N/C_19") (pintype "bidirectional"))
    )
  )
)
